# combined_controller.net
KiCad netlist of a schematic drawn in EAGLE
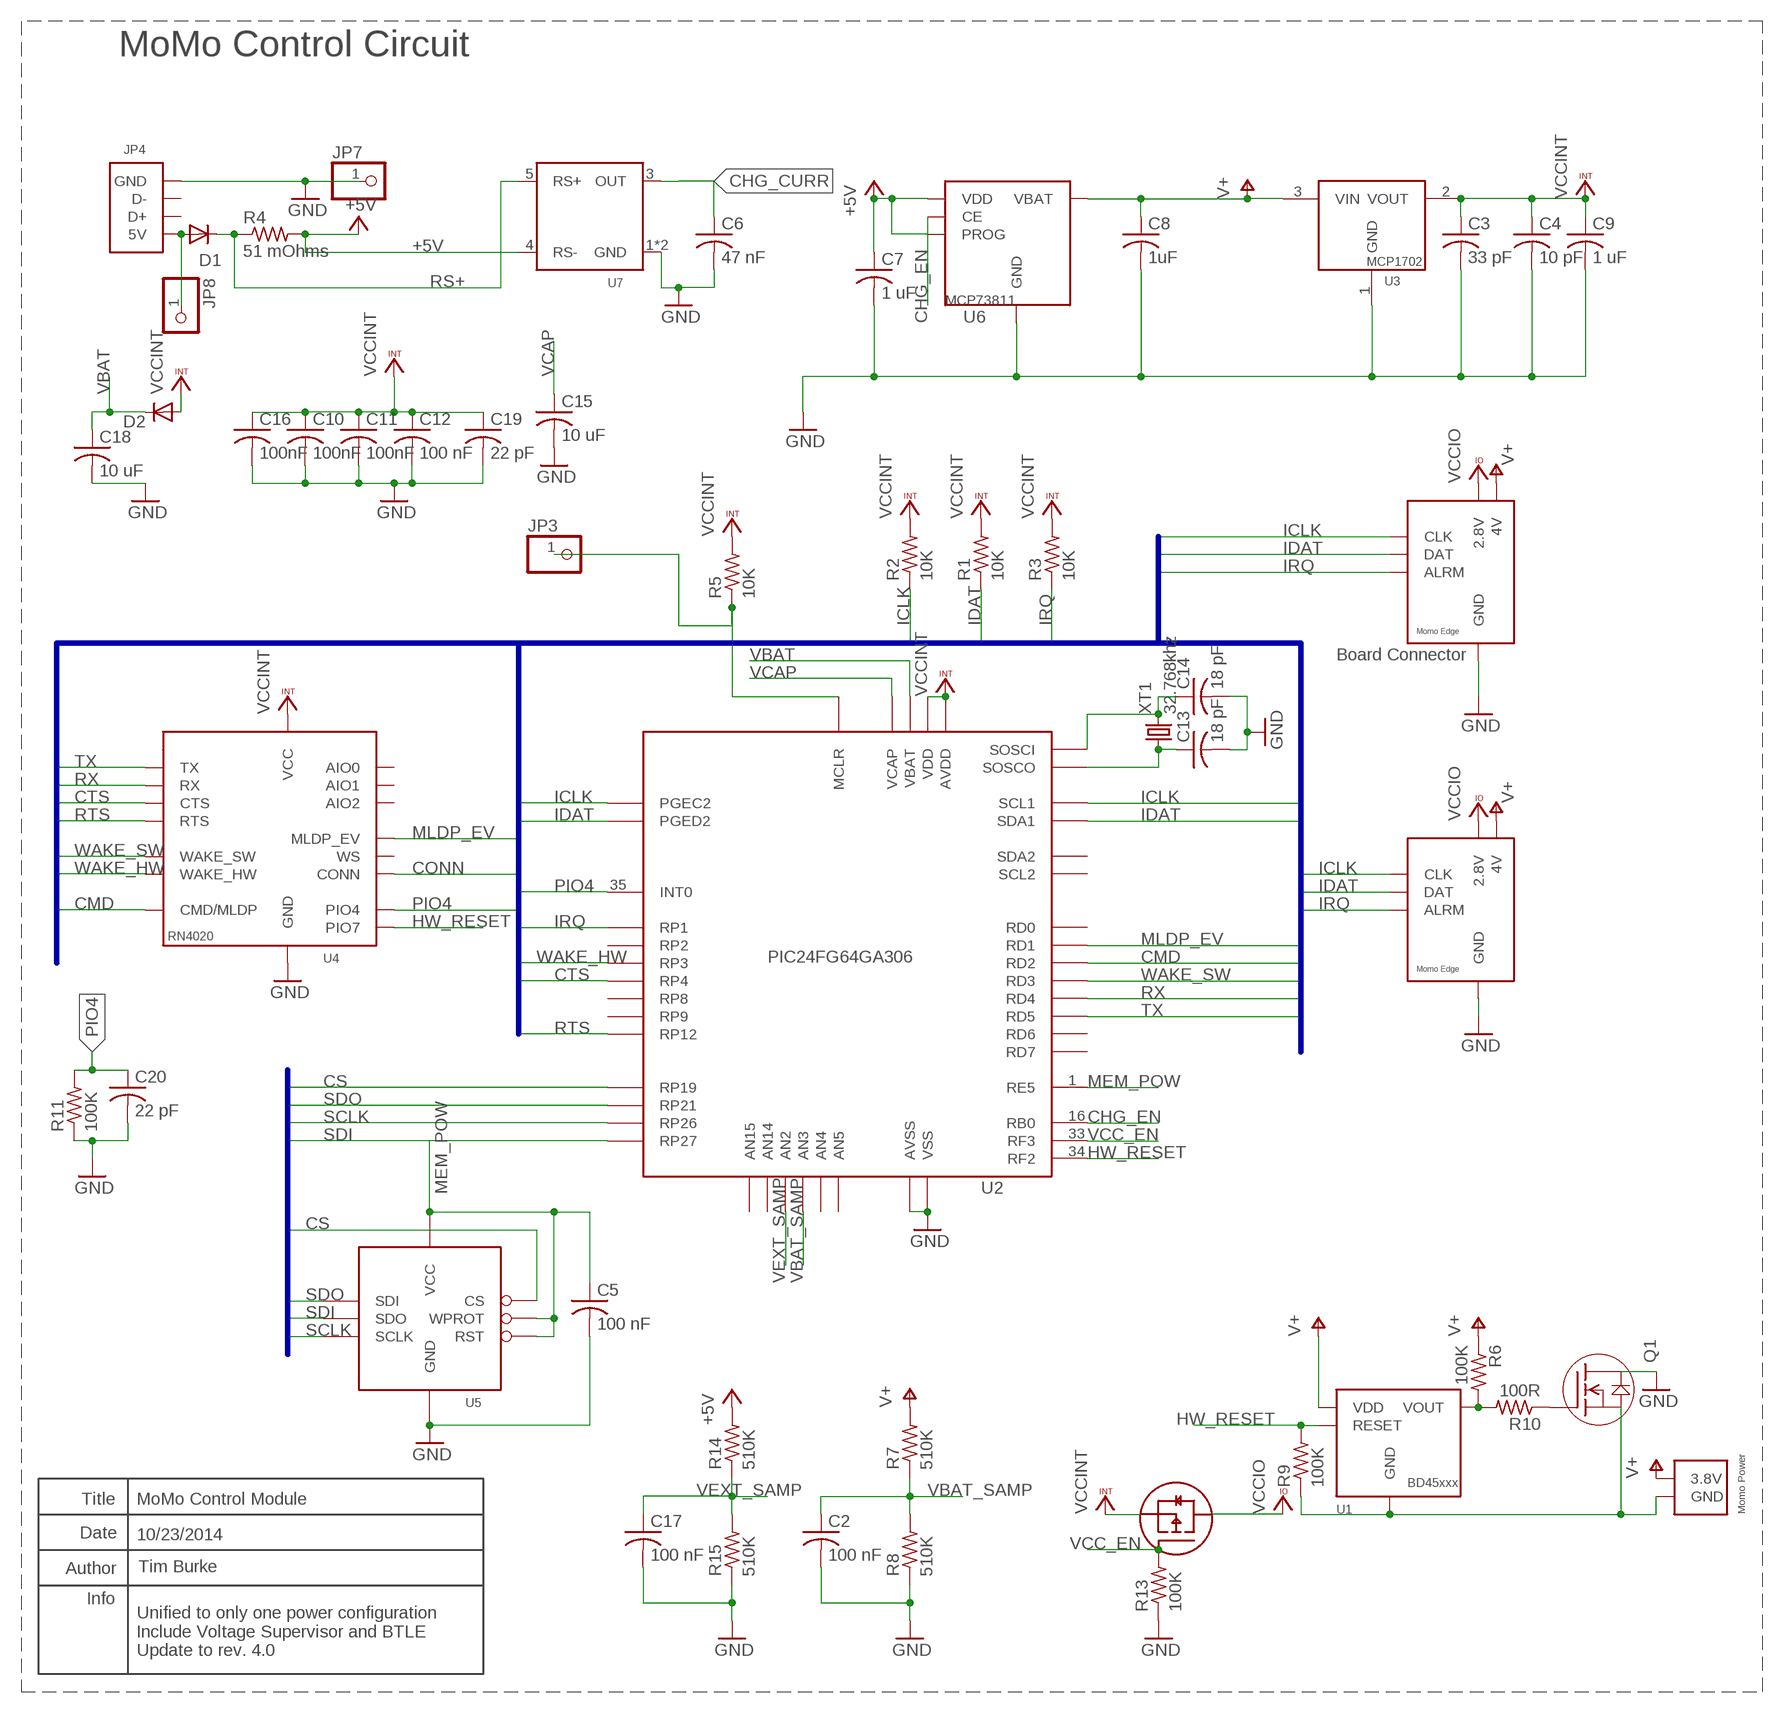
[diagram p0: schematic, sheet 1]

(export (version "E")
  (design (tool "Eeschema 10.0.6"))
  (components
    (comp (ref "C2")
      (value "100 nF")
      (footprint "eagle-import:C0402K")
      (libsource (lib "eagle-import") (part "C-USC0402K"))
    )
    (comp (ref "C3")
      (value "33 pF")
      (footprint "eagle-import:C0402K")
      (libsource (lib "eagle-import") (part "C-USC0402K"))
    )
    (comp (ref "C4")
      (value "10 pF")
      (footprint "eagle-import:C0402K")
      (libsource (lib "eagle-import") (part "C-USC0402K"))
    )
    (comp (ref "C5")
      (value "100 nF")
      (footprint "eagle-import:C0402K")
      (libsource (lib "eagle-import") (part "C-USC0402K"))
    )
    (comp (ref "C6")
      (value "47 nF")
      (footprint "eagle-import:C0402K")
      (libsource (lib "eagle-import") (part "C-USC0402K"))
    )
    (comp (ref "C7")
      (value "1 uF")
      (footprint "eagle-import:C0402K")
      (libsource (lib "eagle-import") (part "C-USC0402K"))
    )
    (comp (ref "C8")
      (value "1uF")
      (footprint "eagle-import:C0402K")
      (libsource (lib "eagle-import") (part "C-USC0402K"))
    )
    (comp (ref "C9")
      (value "1 uF")
      (footprint "eagle-import:C0402K")
      (libsource (lib "eagle-import") (part "C-USC0402K"))
    )
    (comp (ref "C10")
      (value "100nF")
      (footprint "eagle-import:C0402K")
      (libsource (lib "eagle-import") (part "C-USC0402K"))
    )
    (comp (ref "C11")
      (value "100nF")
      (footprint "eagle-import:C0402K")
      (libsource (lib "eagle-import") (part "C-USC0402K"))
    )
    (comp (ref "C12")
      (value "100 nF")
      (footprint "eagle-import:C0402K")
      (libsource (lib "eagle-import") (part "C-USC0402K"))
    )
    (comp (ref "C13")
      (value "18 pF")
      (footprint "eagle-import:C0402K")
      (libsource (lib "eagle-import") (part "C-USC0402K"))
    )
    (comp (ref "C14")
      (value "18 pF")
      (footprint "eagle-import:C0402K")
      (libsource (lib "eagle-import") (part "C-USC0402K"))
    )
    (comp (ref "C15")
      (value "10 uF")
      (footprint "eagle-import:C0805K")
      (libsource (lib "eagle-import") (part "C-USC0805K"))
    )
    (comp (ref "C16")
      (value "100nF")
      (footprint "eagle-import:C0402K")
      (libsource (lib "eagle-import") (part "C-USC0402K"))
    )
    (comp (ref "C17")
      (value "100 nF")
      (footprint "eagle-import:C0402K")
      (libsource (lib "eagle-import") (part "C-USC0402K"))
    )
    (comp (ref "C18")
      (value "10 uF")
      (footprint "eagle-import:C0805K")
      (libsource (lib "eagle-import") (part "C-USC0805K"))
    )
    (comp (ref "C19")
      (value "22 pF")
      (footprint "eagle-import:C0402K")
      (libsource (lib "eagle-import") (part "C-USC0402K"))
    )
    (comp (ref "C20")
      (value "22 pF")
      (footprint "eagle-import:C0402K")
      (libsource (lib "eagle-import") (part "C-USC0402K"))
    )
    (comp (ref "D1")
      (value "DIODE-SC79_INFINEON")
      (footprint "eagle-import:SC79_INFINEON")
      (libsource (lib "eagle-import") (part "DIODE-SC79_INFINEON"))
    )
    (comp (ref "D2")
      (value "DIODE-SC79_INFINEON")
      (footprint "eagle-import:SC79_INFINEON")
      (libsource (lib "eagle-import") (part "DIODE-SC79_INFINEON"))
    )
    (comp (ref "JP1")
      (value "MOMO-VERT-6M")
      (footprint "eagle-import:1X06")
      (libsource (lib "eagle-import") (part "MOMO-VERT-6M"))
    )
    (comp (ref "JP2")
      (value "MOMO-EDGE-6F")
      (footprint "eagle-import:MOMO-EDGE-8F")
      (libsource (lib "eagle-import") (part "MOMO-EDGE-6F"))
    )
    (comp (ref "JP3")
      (value "PINHD-1X1")
      (footprint "eagle-import:1X01")
      (libsource (lib "eagle-import") (part "PINHD-1X1"))
    )
    (comp (ref "JP4")
      (value "CONN-MICROUSB-B-RCPT")
      (footprint "eagle-import:MICROUSB-B-FCI")
      (libsource (lib "eagle-import") (part "CONN-MICROUSB-B-RCPT"))
    )
    (comp (ref "JP5")
      (value "MOMO-PWR-HOUSED")
      (footprint "eagle-import:MOMO-PWR-HOUSED")
      (libsource (lib "eagle-import") (part "MOMO-PWR-HOUSED"))
    )
    (comp (ref "JP7")
      (value "PINHD-1X1")
      (footprint "eagle-import:1X01")
      (libsource (lib "eagle-import") (part "PINHD-1X1"))
    )
    (comp (ref "JP8")
      (value "PINHD-1X1")
      (footprint "eagle-import:1X01")
      (libsource (lib "eagle-import") (part "PINHD-1X1"))
    )
    (comp (ref "Q1")
      (value "MOSFET-N")
      (footprint "eagle-import:SOT-23")
      (libsource (lib "eagle-import") (part "MOSFET-N"))
    )
    (comp (ref "Q2")
      (value "P-MOSFET")
      (footprint "eagle-import:SOT23")
      (description "P Channel MOSFET")
      (libsource (lib "eagle-import") (part "P-MOSFET"))
    )
    (comp (ref "R1")
      (value "10K")
      (footprint "eagle-import:R0603")
      (libsource (lib "eagle-import") (part "R-US_R0603"))
    )
    (comp (ref "R2")
      (value "10K")
      (footprint "eagle-import:R0603")
      (libsource (lib "eagle-import") (part "R-US_R0603"))
    )
    (comp (ref "R3")
      (value "10K")
      (footprint "eagle-import:R0603")
      (libsource (lib "eagle-import") (part "R-US_R0603"))
    )
    (comp (ref "R4")
      (value "51 mOhms")
      (footprint "eagle-import:R0805")
      (libsource (lib "eagle-import") (part "R-US_R0805"))
    )
    (comp (ref "R5")
      (value "10K")
      (footprint "eagle-import:R0603")
      (libsource (lib "eagle-import") (part "R-US_R0603"))
    )
    (comp (ref "R6")
      (value "100K")
      (footprint "eagle-import:R0603")
      (libsource (lib "eagle-import") (part "R-US_R0603"))
    )
    (comp (ref "R7")
      (value "510K")
      (footprint "eagle-import:R0603")
      (libsource (lib "eagle-import") (part "R-US_R0603"))
    )
    (comp (ref "R8")
      (value "510K")
      (footprint "eagle-import:R0603")
      (libsource (lib "eagle-import") (part "R-US_R0603"))
    )
    (comp (ref "R9")
      (value "100K")
      (footprint "eagle-import:R0603")
      (libsource (lib "eagle-import") (part "R-US_R0603"))
    )
    (comp (ref "R10")
      (value "100R")
      (footprint "eagle-import:R0603")
      (libsource (lib "eagle-import") (part "R-US_R0603"))
    )
    (comp (ref "R11")
      (value "100K")
      (footprint "eagle-import:R0603")
      (libsource (lib "eagle-import") (part "R-US_R0603"))
    )
    (comp (ref "R13")
      (value "100K")
      (footprint "eagle-import:R0603")
      (libsource (lib "eagle-import") (part "R-US_R0603"))
    )
    (comp (ref "R14")
      (value "510K")
      (footprint "eagle-import:R0603")
      (libsource (lib "eagle-import") (part "R-US_R0603"))
    )
    (comp (ref "R15")
      (value "510K")
      (footprint "eagle-import:R0603")
      (libsource (lib "eagle-import") (part "R-US_R0603"))
    )
    (comp (ref "U1")
      (value "VOLTAGE-SUPERVISOR-BD45312")
      (footprint "eagle-import:SSOP-5")
      (libsource (lib "eagle-import") (part "VOLTAGE-SUPERVISOR-BD45312"))
    )
    (comp (ref "U2")
      (value "PIC24FJ64GA306")
      (footprint "eagle-import:TQFP64-10X10")
      (libsource (lib "eagle-import") (part "PIC24FJ64GA306"))
    )
    (comp (ref "U3")
      (value "MCP1702")
      (footprint "eagle-import:SOT23")
      (fields (field (name "DIGIKEY-PN") "MCP1702T-2802E/CBCT-ND"))
      (libsource (lib "eagle-import") (part "MCP1702"))
    )
    (comp (ref "U4")
      (value "RN4020_BT_4.0_MODULE")
      (footprint "eagle-import:RN20-BTLE-MODULE")
      (libsource (lib "eagle-import") (part "RN4020_BT_4.0_MODULE"))
    )
    (comp (ref "U5")
      (value "FLASH8MSOP8")
      (footprint "eagle-import:SOP08")
      (fields (field (name "DIGIKEY-PN") "M25PX80-VMN6TPCT-ND"))
      (libsource (lib "eagle-import") (part "FLASH8MSOP8"))
    )
    (comp (ref "U6")
      (value "MCP73811")
      (footprint "eagle-import:SOT23-5L")
      (libsource (lib "eagle-import") (part "MCP73811"))
    )
    (comp (ref "U7")
      (value "TS1102-CURRENT-SENSE")
      (footprint "eagle-import:SOT23-5L")
      (libsource (lib "eagle-import") (part "TS1102-CURRENT-SENSE"))
    )
    (comp (ref "XT1")
      (value "32.768khz")
      (footprint "eagle-import:TC26H")
      (libsource (lib "eagle-import") (part "XTAL-W-CAN-PAD"))
    )
  )
  (nets
    (net (code "1") (name "+5V") (class "Default")
      (node (ref "C7") (pin "1") (pinfunction "1_1") (pintype "passive"))
      (node (ref "R14") (pin "2") (pinfunction "2_2") (pintype "passive"))
      (node (ref "R4") (pin "2") (pinfunction "2_2") (pintype "passive"))
      (node (ref "U6") (pin "4") (pinfunction "VDD_4") (pintype "bidirectional"))
      (node (ref "U6") (pin "5") (pinfunction "PROG_5") (pintype "bidirectional"))
      (node (ref "U7") (pin "4") (pinfunction "RS-_4") (pintype "bidirectional"))
    )
    (net (code "2") (name "/CHG_EN") (class "Default")
      (node (ref "U2") (pin "16") (pinfunction "RB0_16") (pintype "bidirectional"))
      (node (ref "U6") (pin "1") (pinfunction "CE_1") (pintype "bidirectional"))
    )
    (net (code "3") (name "/CMD") (class "Default")
      (node (ref "U2") (pin "50") (pinfunction "RD2_50") (pintype "bidirectional"))
      (node (ref "U4") (pin "CMD/MLDP") (pinfunction "CMD/MLDP_CMD/MLDP") (pintype "bidirectional"))
    )
    (net (code "4") (name "/CONN") (class "Default")
      (node (ref "U4") (pin "PIO1") (pinfunction "CONN_PIO1") (pintype "bidirectional"))
    )
    (net (code "5") (name "/CS") (class "Default")
      (node (ref "U2") (pin "6") (pinfunction "RP19_6") (pintype "bidirectional"))
      (node (ref "U5") (pin "1") (pinfunction "CS_1") (pintype "bidirectional"))
    )
    (net (code "6") (name "/CTS") (class "Default")
      (node (ref "U2") (pin "43") (pinfunction "RP4_43") (pintype "bidirectional"))
      (node (ref "U4") (pin "PIO5") (pinfunction "CTS_PIO5") (pintype "bidirectional"))
    )
    (net (code "7") (name "/HW_RESET") (class "Default")
      (node (ref "R9") (pin "2") (pinfunction "2_2") (pintype "passive"))
      (node (ref "U1") (pin "1") (pinfunction "RESET_1") (pintype "bidirectional"))
      (node (ref "U2") (pin "34") (pinfunction "RF2_34") (pintype "bidirectional"))
      (node (ref "U4") (pin "PIO7") (pinfunction "PIO7_PIO7") (pintype "bidirectional"))
    )
    (net (code "8") (name "/ICLK") (class "Default")
      (node (ref "JP1") (pin "3") (pinfunction "CLK_3") (pintype "bidirectional"))
      (node (ref "JP2") (pin "CLK") (pinfunction "CLK_CLK") (pintype "bidirectional"))
      (node (ref "R2") (pin "1") (pinfunction "1_1") (pintype "passive"))
      (node (ref "U2") (pin "17") (pinfunction "PGEC2_17") (pintype "bidirectional"))
      (node (ref "U2") (pin "37") (pinfunction "SCL1_37") (pintype "bidirectional"))
    )
    (net (code "9") (name "/IDAT") (class "Default")
      (node (ref "JP1") (pin "4") (pinfunction "DAT_4") (pintype "bidirectional"))
      (node (ref "JP2") (pin "DAT") (pinfunction "DAT_DAT") (pintype "bidirectional"))
      (node (ref "R1") (pin "1") (pinfunction "1_1") (pintype "passive"))
      (node (ref "U2") (pin "18") (pinfunction "PGED2_18") (pintype "bidirectional"))
      (node (ref "U2") (pin "36") (pinfunction "SDA1_36") (pintype "bidirectional"))
    )
    (net (code "10") (name "/IRQ") (class "Default")
      (node (ref "JP1") (pin "5") (pinfunction "ALRM_5") (pintype "bidirectional"))
      (node (ref "JP2") (pin "ARLM") (pinfunction "ALRM_ARLM") (pintype "bidirectional"))
      (node (ref "R3") (pin "1") (pinfunction "1_1") (pintype "passive"))
      (node (ref "U2") (pin "15") (pinfunction "RP1_15") (pintype "bidirectional"))
    )
    (net (code "11") (name "/MEM_POW") (class "Default")
      (node (ref "C5") (pin "1") (pinfunction "1_1") (pintype "passive"))
      (node (ref "U2") (pin "1") (pinfunction "RE5_1") (pintype "bidirectional"))
      (node (ref "U5") (pin "3") (pinfunction "WPROT_3") (pintype "bidirectional"))
      (node (ref "U5") (pin "7") (pinfunction "RST_7") (pintype "bidirectional"))
      (node (ref "U5") (pin "8") (pinfunction "VCC_8") (pintype "power_in"))
    )
    (net (code "12") (name "/MLDP_EV") (class "Default")
      (node (ref "U2") (pin "49") (pinfunction "RD1_49") (pintype "bidirectional"))
      (node (ref "U4") (pin "PIO2") (pinfunction "MLDP_EV_PIO2") (pintype "bidirectional"))
    )
    (net (code "13") (name "/RS+") (class "Default")
      (node (ref "D1") (pin "C") (pinfunction "C_C") (pintype "passive"))
      (node (ref "R4") (pin "1") (pinfunction "1_1") (pintype "passive"))
      (node (ref "U7") (pin "5") (pinfunction "RS+_5") (pintype "bidirectional"))
    )
    (net (code "14") (name "/RTS") (class "Default")
      (node (ref "U2") (pin "45") (pinfunction "RP12_45") (pintype "bidirectional"))
      (node (ref "U4") (pin "RTS/PIO6") (pinfunction "RTS_RTS/PIO6") (pintype "bidirectional"))
    )
    (net (code "15") (name "/RX") (class "Default")
      (node (ref "U2") (pin "52") (pinfunction "RD4_52") (pintype "bidirectional"))
      (node (ref "U4") (pin "UART_RX") (pinfunction "RX_UART_RX") (pintype "bidirectional"))
    )
    (net (code "16") (name "/SCLK") (class "Default")
      (node (ref "U2") (pin "5") (pinfunction "RP26_5") (pintype "bidirectional"))
      (node (ref "U5") (pin "6") (pinfunction "SCLK_6") (pintype "bidirectional"))
    )
    (net (code "17") (name "/SDI") (class "Default")
      (node (ref "U2") (pin "8") (pinfunction "RP27_8") (pintype "bidirectional"))
      (node (ref "U5") (pin "2") (pinfunction "SDO_2") (pintype "bidirectional"))
    )
    (net (code "18") (name "/SDO") (class "Default")
      (node (ref "U2") (pin "4") (pinfunction "RP21_4") (pintype "bidirectional"))
      (node (ref "U5") (pin "5") (pinfunction "SDI_5") (pintype "bidirectional"))
    )
    (net (code "19") (name "/TX") (class "Default")
      (node (ref "U2") (pin "53") (pinfunction "RD5_53") (pintype "bidirectional"))
      (node (ref "U4") (pin "UART_TX") (pinfunction "TX_UART_TX") (pintype "bidirectional"))
    )
    (net (code "20") (name "/VBAT") (class "Default")
      (node (ref "C18") (pin "1") (pinfunction "1_1") (pintype "passive"))
      (node (ref "D2") (pin "C") (pinfunction "C_C") (pintype "passive"))
      (node (ref "U2") (pin "57") (pinfunction "VBAT_57") (pintype "bidirectional"))
    )
    (net (code "21") (name "/VBAT_SAMP") (class "Default")
      (node (ref "C2") (pin "1") (pinfunction "1_1") (pintype "passive"))
      (node (ref "R7") (pin "1") (pinfunction "1_1") (pintype "passive"))
      (node (ref "R8") (pin "2") (pinfunction "2_2") (pintype "passive"))
      (node (ref "U2") (pin "13") (pinfunction "AN3_13") (pintype "bidirectional"))
    )
    (net (code "22") (name "/VCAP") (class "Default")
      (node (ref "C15") (pin "1") (pinfunction "1_1") (pintype "passive"))
      (node (ref "U2") (pin "56") (pinfunction "VCAP_56") (pintype "bidirectional"))
    )
    (net (code "23") (name "/VCC_EN") (class "Default")
      (node (ref "Q2") (pin "1") (pinfunction "GATE_1") (pintype "bidirectional"))
      (node (ref "R13") (pin "2") (pinfunction "2_2") (pintype "passive"))
      (node (ref "U2") (pin "33") (pinfunction "RF3_33") (pintype "bidirectional"))
    )
    (net (code "24") (name "/VEXT_SAMP") (class "Default")
      (node (ref "C17") (pin "1") (pinfunction "1_1") (pintype "passive"))
      (node (ref "R14") (pin "1") (pinfunction "1_1") (pintype "passive"))
      (node (ref "R15") (pin "2") (pinfunction "2_2") (pintype "passive"))
      (node (ref "U2") (pin "14") (pinfunction "AN2_14") (pintype "bidirectional"))
    )
    (net (code "25") (name "/WAKE_HW") (class "Default")
      (node (ref "U2") (pin "44") (pinfunction "RP3_44") (pintype "bidirectional"))
      (node (ref "U4") (pin "WAKE_HW") (pinfunction "WAKE_HW_WAKE_HW") (pintype "bidirectional"))
    )
    (net (code "26") (name "/WAKE_SW") (class "Default")
      (node (ref "U2") (pin "51") (pinfunction "RD3_51") (pintype "bidirectional"))
      (node (ref "U4") (pin "WAKE_SW") (pinfunction "WAKE_SW_WAKE_SW") (pintype "bidirectional"))
    )
    (net (code "27") (name "CHG_CURR") (class "Default")
      (node (ref "C6") (pin "1") (pinfunction "1_1") (pintype "passive"))
      (node (ref "U7") (pin "3") (pinfunction "OUT_3") (pintype "bidirectional"))
    )
    (net (code "28") (name "GND") (class "Default")
      (node (ref "C10") (pin "2") (pinfunction "2_2") (pintype "passive"))
      (node (ref "C11") (pin "2") (pinfunction "2_2") (pintype "passive"))
      (node (ref "C12") (pin "2") (pinfunction "2_2") (pintype "passive"))
      (node (ref "C13") (pin "2") (pinfunction "2_2") (pintype "passive"))
      (node (ref "C14") (pin "2") (pinfunction "2_2") (pintype "passive"))
      (node (ref "C15") (pin "2") (pinfunction "2_2") (pintype "passive"))
      (node (ref "C16") (pin "2") (pinfunction "2_2") (pintype "passive"))
      (node (ref "C17") (pin "2") (pinfunction "2_2") (pintype "passive"))
      (node (ref "C18") (pin "2") (pinfunction "2_2") (pintype "passive"))
      (node (ref "C19") (pin "2") (pinfunction "2_2") (pintype "passive"))
      (node (ref "C2") (pin "2") (pinfunction "2_2") (pintype "passive"))
      (node (ref "C20") (pin "2") (pinfunction "2_2") (pintype "passive"))
      (node (ref "C3") (pin "2") (pinfunction "2_2") (pintype "passive"))
      (node (ref "C4") (pin "2") (pinfunction "2_2") (pintype "passive"))
      (node (ref "C5") (pin "2") (pinfunction "2_2") (pintype "passive"))
      (node (ref "C6") (pin "2") (pinfunction "2_2") (pintype "passive"))
      (node (ref "C7") (pin "2") (pinfunction "2_2") (pintype "passive"))
      (node (ref "C8") (pin "2") (pinfunction "2_2") (pintype "passive"))
      (node (ref "C9") (pin "2") (pinfunction "2_2") (pintype "passive"))
      (node (ref "JP1") (pin "7") (pinfunction "GND_7") (pintype "power_in"))
      (node (ref "JP2") (pin "GND") (pinfunction "GND_GND") (pintype "power_in"))
      (node (ref "JP4") (pin "5") (pinfunction "GND_5") (pintype "power_in"))
      (node (ref "JP4") (pin "GND1") (pinfunction "GND_GND1") (pintype "power_in"))
      (node (ref "JP4") (pin "GND2") (pinfunction "GND_GND2") (pintype "power_in"))
      (node (ref "JP4") (pin "GND3") (pinfunction "GND_GND3") (pintype "power_in"))
      (node (ref "JP4") (pin "GND4") (pinfunction "GND_GND4") (pintype "power_in"))
      (node (ref "JP4") (pin "GND5") (pinfunction "GND_GND5") (pintype "power_in"))
      (node (ref "JP4") (pin "GND6") (pinfunction "GND_GND6") (pintype "power_in"))
      (node (ref "JP7") (pin "1") (pinfunction "1_1") (pintype "passive"))
      (node (ref "Q1") (pin "3") (pinfunction "D_3") (pintype "passive"))
      (node (ref "R11") (pin "1") (pinfunction "1_1") (pintype "passive"))
      (node (ref "R13") (pin "1") (pinfunction "1_1") (pintype "passive"))
      (node (ref "R15") (pin "1") (pinfunction "1_1") (pintype "passive"))
      (node (ref "R8") (pin "1") (pinfunction "1_1") (pintype "passive"))
      (node (ref "U2") (pin "20") (pinfunction "AVSS_20") (pintype "bidirectional"))
      (node (ref "U2") (pin "25") (pinfunction "VSS_25") (pintype "bidirectional"))
      (node (ref "U2") (pin "41") (pinfunction "VSS_41") (pintype "bidirectional"))
      (node (ref "U2") (pin "9") (pinfunction "VSS_9") (pintype "bidirectional"))
      (node (ref "U3") (pin "1") (pinfunction "GND_1") (pintype "bidirectional"))
      (node (ref "U4") (pin "GND") (pinfunction "GND_GND") (pintype "bidirectional"))
      (node (ref "U4") (pin "GND1") (pinfunction "GND_GND1") (pintype "bidirectional"))
      (node (ref "U4") (pin "SHIELD1") (pinfunction "GND_SHIELD1") (pintype "bidirectional"))
      (node (ref "U4") (pin "SHIELD2") (pinfunction "GND_SHIELD2") (pintype "bidirectional"))
      (node (ref "U4") (pin "SHIELD3") (pinfunction "GND_SHIELD3") (pintype "bidirectional"))
      (node (ref "U4") (pin "SHIELD4") (pinfunction "GND_SHIELD4") (pintype "bidirectional"))
      (node (ref "U5") (pin "4") (pinfunction "GND_4") (pintype "power_in"))
      (node (ref "U6") (pin "2") (pinfunction "GND_2") (pintype "bidirectional"))
      (node (ref "U7") (pin "1") (pinfunction "GND_1") (pintype "bidirectional"))
      (node (ref "U7") (pin "2") (pinfunction "GND_2") (pintype "bidirectional"))
    )
    (net (code "29") (name "Net-(JP4-5V)") (class "Default")
      (node (ref "D1") (pin "A") (pinfunction "A_A") (pintype "passive"))
      (node (ref "JP4") (pin "1") (pinfunction "5V_1") (pintype "power_in"))
      (node (ref "JP8") (pin "1") (pinfunction "1_1") (pintype "passive"))
    )
    (net (code "30") (name "Net-(JP5-GND)") (class "Default")
      (node (ref "JP5") (pin "2") (pinfunction "GND_2") (pintype "power_in"))
      (node (ref "Q1") (pin "2") (pinfunction "S_2") (pintype "passive"))
      (node (ref "R9") (pin "1") (pinfunction "1_1") (pintype "passive"))
      (node (ref "U1") (pin "2") (pinfunction "GND_2") (pintype "power_in"))
      (node (ref "U1") (pin "3") (pinfunction "GND_3") (pintype "power_in"))
    )
    (net (code "31") (name "Net-(Q1-G)") (class "Default")
      (node (ref "Q1") (pin "1") (pinfunction "G_1") (pintype "passive"))
      (node (ref "R10") (pin "1") (pinfunction "1_1") (pintype "passive"))
    )
    (net (code "32") (name "Net-(U1-VOUT)") (class "Default")
      (node (ref "R10") (pin "2") (pinfunction "2_2") (pintype "passive"))
      (node (ref "R6") (pin "2") (pinfunction "2_2") (pintype "passive"))
      (node (ref "U1") (pin "4") (pinfunction "VOUT_4") (pintype "bidirectional"))
    )
    (net (code "33") (name "Net-(U2-MCLR)") (class "Default")
      (node (ref "JP3") (pin "1") (pinfunction "1_1") (pintype "passive"))
      (node (ref "R5") (pin "1") (pinfunction "1_1") (pintype "passive"))
      (node (ref "U2") (pin "7") (pinfunction "MCLR_7") (pintype "bidirectional"))
    )
    (net (code "34") (name "Net-(U2-SOSCI)") (class "Default")
      (node (ref "C14") (pin "1") (pinfunction "1_1") (pintype "passive"))
      (node (ref "U2") (pin "47") (pinfunction "SOSCI_47") (pintype "bidirectional"))
      (node (ref "XT1") (pin "2") (pinfunction "2_2") (pintype "passive"))
    )
    (net (code "35") (name "Net-(U2-SOSCO)") (class "Default")
      (node (ref "C13") (pin "1") (pinfunction "1_1") (pintype "passive"))
      (node (ref "U2") (pin "48") (pinfunction "SOSCO_48") (pintype "bidirectional"))
      (node (ref "XT1") (pin "1") (pinfunction "1_1") (pintype "passive"))
    )
    (net (code "36") (name "PIO4") (class "Default")
      (node (ref "C20") (pin "1") (pinfunction "1_1") (pintype "passive"))
      (node (ref "R11") (pin "2") (pinfunction "2_2") (pintype "passive"))
      (node (ref "U2") (pin "35") (pinfunction "INT0_35") (pintype "bidirectional"))
      (node (ref "U4") (pin "PIO4") (pinfunction "PIO4_PIO4") (pintype "bidirectional"))
    )
    (net (code "37") (name "V+") (class "Default")
      (node (ref "C8") (pin "1") (pinfunction "1_1") (pintype "passive"))
      (node (ref "JP1") (pin "6") (pinfunction "4V_6") (pintype "power_in"))
      (node (ref "JP2") (pin "V4") (pinfunction "4V_V4") (pintype "power_in"))
      (node (ref "JP5") (pin "1") (pinfunction "3.8V_1") (pintype "power_in"))
      (node (ref "R6") (pin "1") (pinfunction "1_1") (pintype "passive"))
      (node (ref "R7") (pin "2") (pinfunction "2_2") (pintype "passive"))
      (node (ref "U1") (pin "5") (pinfunction "VDD_5") (pintype "power_in"))
      (node (ref "U3") (pin "3") (pinfunction "VIN_3") (pintype "bidirectional"))
      (node (ref "U6") (pin "3") (pinfunction "VBAT_3") (pintype "bidirectional"))
    )
    (net (code "38") (name "VCCINT") (class "Default")
      (node (ref "C10") (pin "1") (pinfunction "1_1") (pintype "passive"))
      (node (ref "C11") (pin "1") (pinfunction "1_1") (pintype "passive"))
      (node (ref "C12") (pin "1") (pinfunction "1_1") (pintype "passive"))
      (node (ref "C16") (pin "1") (pinfunction "1_1") (pintype "passive"))
      (node (ref "C19") (pin "1") (pinfunction "1_1") (pintype "passive"))
      (node (ref "C3") (pin "1") (pinfunction "1_1") (pintype "passive"))
      (node (ref "C4") (pin "1") (pinfunction "1_1") (pintype "passive"))
      (node (ref "C9") (pin "1") (pinfunction "1_1") (pintype "passive"))
      (node (ref "D2") (pin "A") (pinfunction "A_A") (pintype "passive"))
      (node (ref "Q2") (pin "2") (pinfunction "SOURCE_2") (pintype "bidirectional"))
      (node (ref "R1") (pin "2") (pinfunction "2_2") (pintype "passive"))
      (node (ref "R2") (pin "2") (pinfunction "2_2") (pintype "passive"))
      (node (ref "R3") (pin "2") (pinfunction "2_2") (pintype "passive"))
      (node (ref "R5") (pin "2") (pinfunction "2_2") (pintype "passive"))
      (node (ref "U2") (pin "10") (pinfunction "VDD_10") (pintype "bidirectional"))
      (node (ref "U2") (pin "19") (pinfunction "AVDD_19") (pintype "bidirectional"))
      (node (ref "U2") (pin "26") (pinfunction "VDD_26") (pintype "bidirectional"))
      (node (ref "U2") (pin "38") (pinfunction "VDD_38") (pintype "bidirectional"))
      (node (ref "U3") (pin "2") (pinfunction "VOUT_2") (pintype "bidirectional"))
      (node (ref "U4") (pin "VDD") (pinfunction "VCC_VDD") (pintype "bidirectional"))
    )
    (net (code "39") (name "VCCIO") (class "Default")
      (node (ref "JP1") (pin "1") (pinfunction "2.8V_1") (pintype "power_in"))
      (node (ref "JP2") (pin "V28") (pinfunction "2.8V_V28") (pintype "power_in"))
      (node (ref "Q2") (pin "3") (pinfunction "DRAIN_3") (pintype "bidirectional"))
    )
    (net (code "40") (name "unconnected-(JP4-D+-Pad3)") (class "Default")
      (node (ref "JP4") (pin "3") (pinfunction "D+_3") (pintype "bidirectional"))
    )
    (net (code "41") (name "unconnected-(JP4-D--Pad2)") (class "Default")
      (node (ref "JP4") (pin "2") (pinfunction "D-_2") (pintype "bidirectional"))
    )
    (net (code "42") (name "unconnected-(U2-AN4-Pad12)") (class "Default")
      (node (ref "U2") (pin "12") (pinfunction "AN4_12") (pintype "bidirectional"))
    )
    (net (code "43") (name "unconnected-(U2-AN5-Pad11)") (class "Default")
      (node (ref "U2") (pin "11") (pinfunction "AN5_11") (pintype "bidirectional"))
    )
    (net (code "44") (name "unconnected-(U2-AN14-Pad29)") (class "Default")
      (node (ref "U2") (pin "29") (pinfunction "AN14_29") (pintype "bidirectional"))
    )
    (net (code "45") (name "unconnected-(U2-AN15-Pad30)") (class "Default")
      (node (ref "U2") (pin "30") (pinfunction "AN15_30") (pintype "bidirectional"))
    )
    (net (code "46") (name "unconnected-(U2-RD0-Pad46)") (class "Default")
      (node (ref "U2") (pin "46") (pinfunction "RD0_46") (pintype "bidirectional"))
    )
    (net (code "47") (name "unconnected-(U2-RD6-Pad54)") (class "Default")
      (node (ref "U2") (pin "54") (pinfunction "RD6_54") (pintype "bidirectional"))
    )
    (net (code "48") (name "unconnected-(U2-RD7-Pad55)") (class "Default")
      (node (ref "U2") (pin "55") (pinfunction "RD7_55") (pintype "bidirectional"))
    )
    (net (code "49") (name "unconnected-(U2-RP2-Pad42)") (class "Default")
      (node (ref "U2") (pin "42") (pinfunction "RP2_42") (pintype "bidirectional"))
    )
    (net (code "50") (name "unconnected-(U2-RP8-Pad21)") (class "Default")
      (node (ref "U2") (pin "21") (pinfunction "RP8_21") (pintype "bidirectional"))
    )
    (net (code "51") (name "unconnected-(U2-RP9-Pad22)") (class "Default")
      (node (ref "U2") (pin "22") (pinfunction "RP9_22") (pintype "bidirectional"))
    )
    (net (code "52") (name "unconnected-(U2-SCL2-Pad32)") (class "Default")
      (node (ref "U2") (pin "32") (pinfunction "SCL2_32") (pintype "bidirectional"))
    )
    (net (code "53") (name "unconnected-(U2-SDA2-Pad31)") (class "Default")
      (node (ref "U2") (pin "31") (pinfunction "SDA2_31") (pintype "bidirectional"))
    )
    (net (code "54") (name "unconnected-(U4-PadAIO0)") (class "Default")
      (node (ref "U4") (pin "AIO0") (pinfunction "AIO0_AIO0") (pintype "bidirectional"))
    )
    (net (code "55") (name "unconnected-(U4-PadAIO1)") (class "Default")
      (node (ref "U4") (pin "AIO1") (pinfunction "AIO1_AIO1") (pintype "bidirectional"))
    )
    (net (code "56") (name "unconnected-(U4-PadAIO2)") (class "Default")
      (node (ref "U4") (pin "AIO2") (pinfunction "AIO2_AIO2") (pintype "bidirectional"))
    )
    (net (code "57") (name "unconnected-(U4-WS-PadPIO3)") (class "Default")
      (node (ref "U4") (pin "PIO3") (pinfunction "WS_PIO3") (pintype "bidirectional"))
    )
  )
)
